# AquModule2.net
KiCad netlist of a schematic drawn in EAGLE
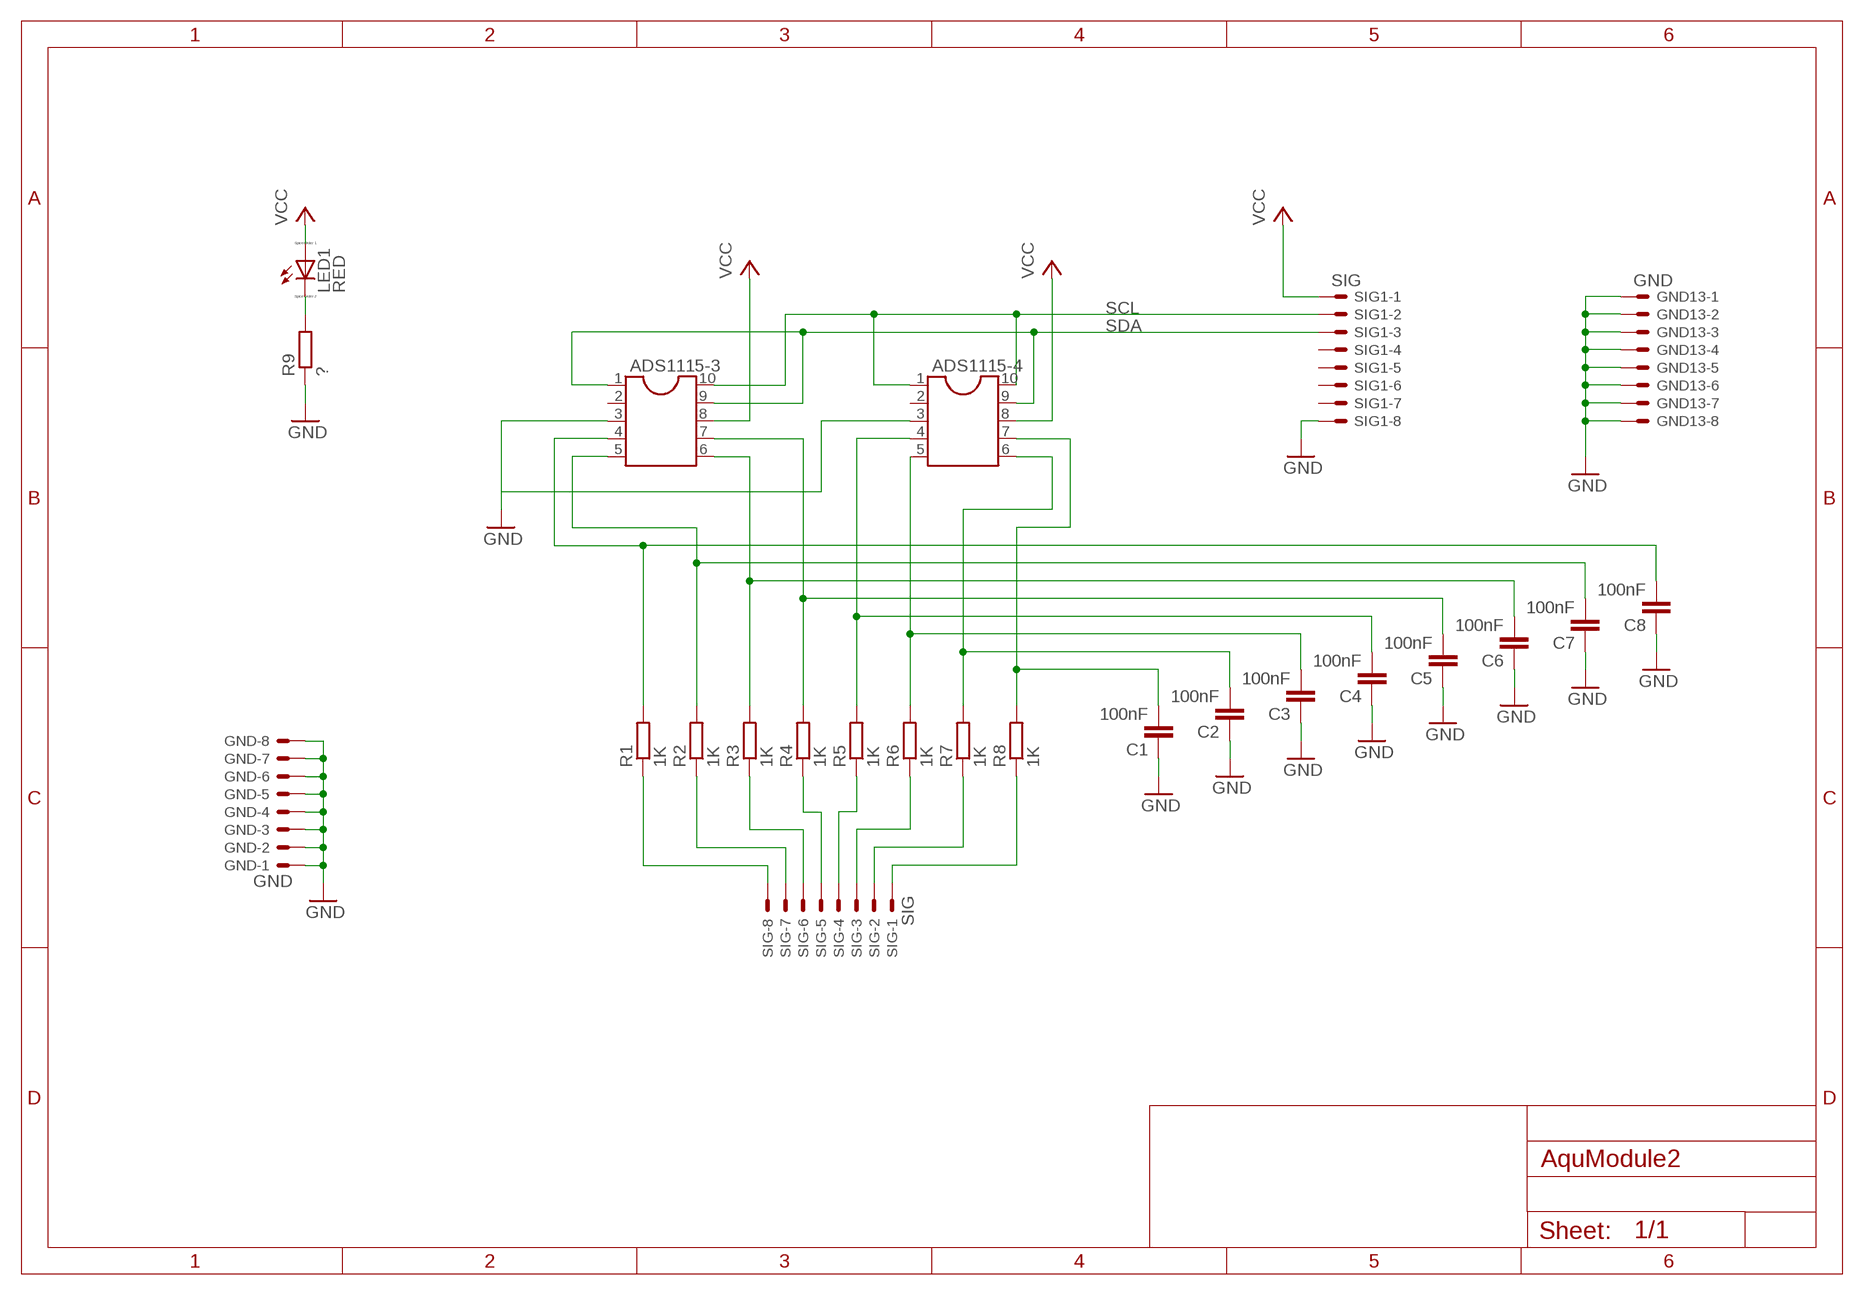
[diagram p0: schematic, sheet 1]

(export (version "E")
  (design (tool "Eeschema 10.0.6"))
  (components
    (comp (ref "ADS1115-3")
      (value "DIL10")
      (footprint "eagle-import:DIL10")
      (libsource (lib "eagle-import") (part "DIL10"))
    )
    (comp (ref "ADS1115-4")
      (value "DIL10")
      (footprint "eagle-import:DIL10")
      (libsource (lib "eagle-import") (part "DIL10"))
    )
    (comp (ref "C1")
      (value "100nF")
      (footprint "eagle-import:C1206")
      (libsource (lib "eagle-import") (part "C-EUC1206"))
    )
    (comp (ref "C2")
      (value "100nF")
      (footprint "eagle-import:C1206")
      (libsource (lib "eagle-import") (part "C-EUC1206"))
    )
    (comp (ref "C3")
      (value "100nF")
      (footprint "eagle-import:C1206")
      (libsource (lib "eagle-import") (part "C-EUC1206"))
    )
    (comp (ref "C4")
      (value "100nF")
      (footprint "eagle-import:C1206")
      (libsource (lib "eagle-import") (part "C-EUC1206"))
    )
    (comp (ref "C5")
      (value "100nF")
      (footprint "eagle-import:C1206")
      (libsource (lib "eagle-import") (part "C-EUC1206"))
    )
    (comp (ref "C6")
      (value "100nF")
      (footprint "eagle-import:C1206")
      (libsource (lib "eagle-import") (part "C-EUC1206"))
    )
    (comp (ref "C7")
      (value "100nF")
      (footprint "eagle-import:C1206")
      (libsource (lib "eagle-import") (part "C-EUC1206"))
    )
    (comp (ref "C8")
      (value "100nF")
      (footprint "eagle-import:C1206")
      (libsource (lib "eagle-import") (part "C-EUC1206"))
    )
    (comp (ref "GND")
      (value "GND")
      (footprint "eagle-import:15-91-08")
      (libsource (lib "eagle-import") (part "C-GRID-08-15-91"))
    )
    (comp (ref "GND13")
      (value "GND")
      (footprint "eagle-import:15-91-08")
      (libsource (lib "eagle-import") (part "C-GRID-08-15-91"))
    )
    (comp (ref "LED1")
      (value "RED")
      (footprint "eagle-import:LED_LD260")
      (libsource (lib "eagle-import") (part "LED_ELD260"))
    )
    (comp (ref "R1")
      (value "1K")
      (footprint "eagle-import:R1206")
      (libsource (lib "eagle-import") (part "R-EU_R1206"))
    )
    (comp (ref "R2")
      (value "1K")
      (footprint "eagle-import:R1206")
      (libsource (lib "eagle-import") (part "R-EU_R1206"))
    )
    (comp (ref "R3")
      (value "1K")
      (footprint "eagle-import:R1206")
      (libsource (lib "eagle-import") (part "R-EU_R1206"))
    )
    (comp (ref "R4")
      (value "1K")
      (footprint "eagle-import:R1206")
      (libsource (lib "eagle-import") (part "R-EU_R1206"))
    )
    (comp (ref "R5")
      (value "1K")
      (footprint "eagle-import:R1206")
      (libsource (lib "eagle-import") (part "R-EU_R1206"))
    )
    (comp (ref "R6")
      (value "1K")
      (footprint "eagle-import:R1206")
      (libsource (lib "eagle-import") (part "R-EU_R1206"))
    )
    (comp (ref "R7")
      (value "1K")
      (footprint "eagle-import:R1206")
      (libsource (lib "eagle-import") (part "R-EU_R1206"))
    )
    (comp (ref "R8")
      (value "1K")
      (footprint "eagle-import:R1206")
      (libsource (lib "eagle-import") (part "R-EU_R1206"))
    )
    (comp (ref "R9")
      (value "?")
      (footprint "eagle-import:0207_2V")
      (libsource (lib "eagle-import") (part "R-EU_0207/2V"))
    )
    (comp (ref "SIG")
      (value "SIG")
      (footprint "eagle-import:15-91-08")
      (libsource (lib "eagle-import") (part "C-GRID-08-15-91"))
    )
    (comp (ref "SIG1")
      (value "SIG")
      (footprint "eagle-import:15-91-08")
      (libsource (lib "eagle-import") (part "C-GRID-08-15-91"))
    )
  )
  (nets
    (net (code "1") (name "/SCL") (class "Default")
      (node (ref "ADS1115-3") (pin "10") (pinfunction "10_10") (pintype "passive"))
      (node (ref "ADS1115-4") (pin "1") (pinfunction "1_1") (pintype "passive"))
      (node (ref "ADS1115-4") (pin "10") (pinfunction "10_10") (pintype "passive"))
      (node (ref "SIG1") (pin "2") (pinfunction "S_2") (pintype "passive"))
    )
    (net (code "2") (name "/SDA") (class "Default")
      (node (ref "ADS1115-3") (pin "1") (pinfunction "1_1") (pintype "passive"))
      (node (ref "ADS1115-3") (pin "9") (pinfunction "9_9") (pintype "passive"))
      (node (ref "ADS1115-4") (pin "9") (pinfunction "9_9") (pintype "passive"))
      (node (ref "SIG1") (pin "3") (pinfunction "S_3") (pintype "passive"))
    )
    (net (code "3") (name "GND") (class "Default")
      (node (ref "ADS1115-3") (pin "3") (pinfunction "3_3") (pintype "passive"))
      (node (ref "ADS1115-4") (pin "3") (pinfunction "3_3") (pintype "passive"))
      (node (ref "C1") (pin "1") (pinfunction "1_1") (pintype "passive"))
      (node (ref "C2") (pin "1") (pinfunction "1_1") (pintype "passive"))
      (node (ref "C3") (pin "1") (pinfunction "1_1") (pintype "passive"))
      (node (ref "C4") (pin "1") (pinfunction "1_1") (pintype "passive"))
      (node (ref "C5") (pin "1") (pinfunction "1_1") (pintype "passive"))
      (node (ref "C6") (pin "1") (pinfunction "1_1") (pintype "passive"))
      (node (ref "C7") (pin "1") (pinfunction "1_1") (pintype "passive"))
      (node (ref "C8") (pin "1") (pinfunction "1_1") (pintype "passive"))
      (node (ref "GND") (pin "1") (pinfunction "S_1") (pintype "passive"))
      (node (ref "GND") (pin "2") (pinfunction "S_2") (pintype "passive"))
      (node (ref "GND") (pin "3") (pinfunction "S_3") (pintype "passive"))
      (node (ref "GND") (pin "4") (pinfunction "S_4") (pintype "passive"))
      (node (ref "GND") (pin "5") (pinfunction "S_5") (pintype "passive"))
      (node (ref "GND") (pin "6") (pinfunction "S_6") (pintype "passive"))
      (node (ref "GND") (pin "7") (pinfunction "S_7") (pintype "passive"))
      (node (ref "GND") (pin "8") (pinfunction "S_8") (pintype "passive"))
      (node (ref "GND13") (pin "1") (pinfunction "S_1") (pintype "passive"))
      (node (ref "GND13") (pin "2") (pinfunction "S_2") (pintype "passive"))
      (node (ref "GND13") (pin "3") (pinfunction "S_3") (pintype "passive"))
      (node (ref "GND13") (pin "4") (pinfunction "S_4") (pintype "passive"))
      (node (ref "GND13") (pin "5") (pinfunction "S_5") (pintype "passive"))
      (node (ref "GND13") (pin "6") (pinfunction "S_6") (pintype "passive"))
      (node (ref "GND13") (pin "7") (pinfunction "S_7") (pintype "passive"))
      (node (ref "GND13") (pin "8") (pinfunction "S_8") (pintype "passive"))
      (node (ref "R9") (pin "1") (pinfunction "1_1") (pintype "passive"))
      (node (ref "SIG1") (pin "8") (pinfunction "S_8") (pintype "passive"))
    )
    (net (code "4") (name "Net-(ADS1115-3-Pad4)") (class "Default")
      (node (ref "ADS1115-3") (pin "4") (pinfunction "4_4") (pintype "passive"))
      (node (ref "C8") (pin "2") (pinfunction "2_2") (pintype "passive"))
      (node (ref "R1") (pin "2") (pinfunction "2_2") (pintype "passive"))
    )
    (net (code "5") (name "Net-(ADS1115-3-Pad5)") (class "Default")
      (node (ref "ADS1115-3") (pin "5") (pinfunction "5_5") (pintype "passive"))
      (node (ref "C7") (pin "2") (pinfunction "2_2") (pintype "passive"))
      (node (ref "R2") (pin "2") (pinfunction "2_2") (pintype "passive"))
    )
    (net (code "6") (name "Net-(ADS1115-3-Pad6)") (class "Default")
      (node (ref "ADS1115-3") (pin "6") (pinfunction "6_6") (pintype "passive"))
      (node (ref "C6") (pin "2") (pinfunction "2_2") (pintype "passive"))
      (node (ref "R3") (pin "2") (pinfunction "2_2") (pintype "passive"))
    )
    (net (code "7") (name "Net-(ADS1115-3-Pad7)") (class "Default")
      (node (ref "ADS1115-3") (pin "7") (pinfunction "7_7") (pintype "passive"))
      (node (ref "C5") (pin "2") (pinfunction "2_2") (pintype "passive"))
      (node (ref "R4") (pin "2") (pinfunction "2_2") (pintype "passive"))
    )
    (net (code "8") (name "Net-(ADS1115-4-Pad4)") (class "Default")
      (node (ref "ADS1115-4") (pin "4") (pinfunction "4_4") (pintype "passive"))
      (node (ref "C4") (pin "2") (pinfunction "2_2") (pintype "passive"))
      (node (ref "R5") (pin "2") (pinfunction "2_2") (pintype "passive"))
    )
    (net (code "9") (name "Net-(ADS1115-4-Pad5)") (class "Default")
      (node (ref "ADS1115-4") (pin "5") (pinfunction "5_5") (pintype "passive"))
      (node (ref "C3") (pin "2") (pinfunction "2_2") (pintype "passive"))
      (node (ref "R6") (pin "2") (pinfunction "2_2") (pintype "passive"))
    )
    (net (code "10") (name "Net-(ADS1115-4-Pad6)") (class "Default")
      (node (ref "ADS1115-4") (pin "6") (pinfunction "6_6") (pintype "passive"))
      (node (ref "C2") (pin "2") (pinfunction "2_2") (pintype "passive"))
      (node (ref "R7") (pin "2") (pinfunction "2_2") (pintype "passive"))
    )
    (net (code "11") (name "Net-(ADS1115-4-Pad7)") (class "Default")
      (node (ref "ADS1115-4") (pin "7") (pinfunction "7_7") (pintype "passive"))
      (node (ref "C1") (pin "2") (pinfunction "2_2") (pintype "passive"))
      (node (ref "R8") (pin "2") (pinfunction "2_2") (pintype "passive"))
    )
    (net (code "12") (name "Net-(LED1-C)") (class "Default")
      (node (ref "LED1") (pin "K") (pinfunction "C_K") (pintype "passive"))
      (node (ref "R9") (pin "2") (pinfunction "2_2") (pintype "passive"))
    )
    (net (code "13") (name "Net-(SIGA-S)") (class "Default")
      (node (ref "R8") (pin "1") (pinfunction "1_1") (pintype "passive"))
      (node (ref "SIG") (pin "1") (pinfunction "S_1") (pintype "passive"))
    )
    (net (code "14") (name "Net-(SIGB-S)") (class "Default")
      (node (ref "R7") (pin "1") (pinfunction "1_1") (pintype "passive"))
      (node (ref "SIG") (pin "2") (pinfunction "S_2") (pintype "passive"))
    )
    (net (code "15") (name "Net-(SIGC-S)") (class "Default")
      (node (ref "R6") (pin "1") (pinfunction "1_1") (pintype "passive"))
      (node (ref "SIG") (pin "3") (pinfunction "S_3") (pintype "passive"))
    )
    (net (code "16") (name "Net-(SIGD-S)") (class "Default")
      (node (ref "R5") (pin "1") (pinfunction "1_1") (pintype "passive"))
      (node (ref "SIG") (pin "4") (pinfunction "S_4") (pintype "passive"))
    )
    (net (code "17") (name "Net-(SIGE-S)") (class "Default")
      (node (ref "R4") (pin "1") (pinfunction "1_1") (pintype "passive"))
      (node (ref "SIG") (pin "5") (pinfunction "S_5") (pintype "passive"))
    )
    (net (code "18") (name "Net-(SIGF-S)") (class "Default")
      (node (ref "R3") (pin "1") (pinfunction "1_1") (pintype "passive"))
      (node (ref "SIG") (pin "6") (pinfunction "S_6") (pintype "passive"))
    )
    (net (code "19") (name "Net-(SIGG-S)") (class "Default")
      (node (ref "R2") (pin "1") (pinfunction "1_1") (pintype "passive"))
      (node (ref "SIG") (pin "7") (pinfunction "S_7") (pintype "passive"))
    )
    (net (code "20") (name "Net-(SIGH-S)") (class "Default")
      (node (ref "R1") (pin "1") (pinfunction "1_1") (pintype "passive"))
      (node (ref "SIG") (pin "8") (pinfunction "S_8") (pintype "passive"))
    )
    (net (code "21") (name "VCC") (class "Default")
      (node (ref "ADS1115-3") (pin "8") (pinfunction "8_8") (pintype "passive"))
      (node (ref "ADS1115-4") (pin "8") (pinfunction "8_8") (pintype "passive"))
      (node (ref "LED1") (pin "A") (pinfunction "A_A") (pintype "passive"))
      (node (ref "SIG1") (pin "1") (pinfunction "S_1") (pintype "passive"))
    )
    (net (code "22") (name "unconnected-(ADS1115-3-Pad2)") (class "Default")
      (node (ref "ADS1115-3") (pin "2") (pinfunction "2_2") (pintype "passive"))
    )
    (net (code "23") (name "unconnected-(ADS1115-4-Pad2)") (class "Default")
      (node (ref "ADS1115-4") (pin "2") (pinfunction "2_2") (pintype "passive"))
    )
    (net (code "24") (name "unconnected-(SIG1D-S-Pad4)") (class "Default")
      (node (ref "SIG1") (pin "4") (pinfunction "S_4") (pintype "passive"))
    )
    (net (code "25") (name "unconnected-(SIG1E-S-Pad5)") (class "Default")
      (node (ref "SIG1") (pin "5") (pinfunction "S_5") (pintype "passive"))
    )
    (net (code "26") (name "unconnected-(SIG1F-S-Pad6)") (class "Default")
      (node (ref "SIG1") (pin "6") (pinfunction "S_6") (pintype "passive"))
    )
    (net (code "27") (name "unconnected-(SIG1G-S-Pad7)") (class "Default")
      (node (ref "SIG1") (pin "7") (pinfunction "S_7") (pintype "passive"))
    )
  )
)
